# 05_COTS_Avionics.net
KiCad netlist of a schematic drawn in Altium Designer
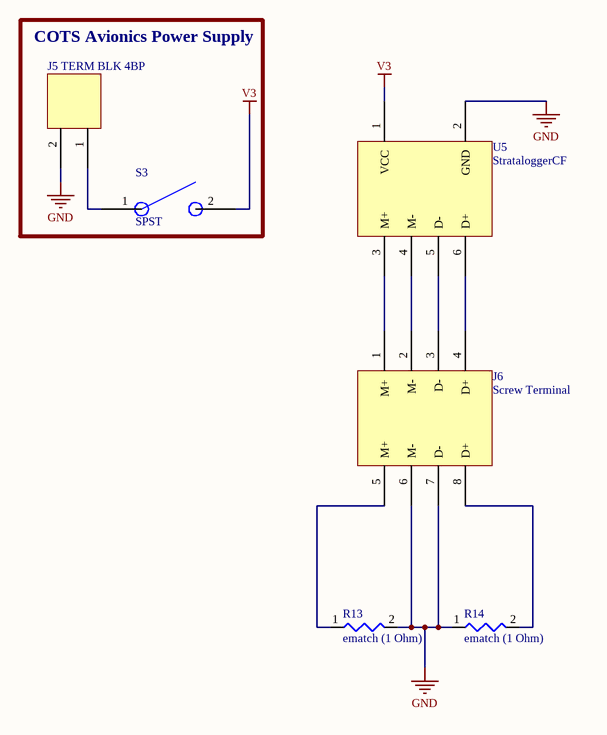
[diagram p0: 05_COTS_Avionics.SchDoc]

(export (version "E")
  (design (tool "Eeschema 10.0.6"))
  (components
    (comp (ref "J5")
      (value "TERM BLK 4BP")
      (footprint "PCB TERM BLK 2P 2.54MM")
      (fields
        (field (name "MANUFACTURER") "TE Connectivity")
        (field (name "MANUFACTURER PART NUMBER") "282834-2")
        (field (name "VOLTAGE") "150V")
      )
      (libsource (lib "SRAD_SAC_Schlib") (part "PCB TERM BLK 2P 2.54MM"))
    )
    (comp (ref "J6")
      (value "Screw Terminal")
      (footprint "Barrier Screw Terminal")
      (libsource (lib "SRAD_SAC_Schlib") (part "Barrier Screw Terminal"))
    )
    (comp (ref "R13")
      (value "ematch (1 Ohm)")
      (footprint "ematch")
      (description "ematch of 1.0-1.5 Ohms of resistance that lights black powder ejection charges.")
      (libsource (lib "SRAD_SAC_Schlib") (part "ematch"))
    )
    (comp (ref "R14")
      (value "ematch (1 Ohm)")
      (footprint "ematch")
      (description "ematch of 1.0-1.5 Ohms of resistance that lights black powder ejection charges.")
      (libsource (lib "SRAD_SAC_Schlib") (part "ematch"))
    )
    (comp (ref "S3")
      (value "SPST")
      (footprint "SPST Switch")
      (description "SPST Switch")
      (libsource (lib "SRAD_SAC_Schlib") (part "SPST Switch"))
    )
    (comp (ref "U5")
      (value "StrataloggerCF")
      (footprint "StrataloggerCF")
      (description "PerfectFlite StrataloggerCF COTS altimeter.")
      (libsource (lib "SRAD_SAC_Schlib") (part "StrataloggerCF"))
    )
  )
  (nets
    (net (code "1") (name "GND") (class "Default")
      (node (ref "J5") (pin "2") (pinfunction "-_2") (pintype "passive"))
      (node (ref "J6") (pin "6") (pinfunction "M-_6") (pintype "passive"))
      (node (ref "J6") (pin "7") (pinfunction "D-_7") (pintype "passive"))
      (node (ref "R13") (pin "2") (pinfunction "-_2") (pintype "passive"))
      (node (ref "R14") (pin "1") (pinfunction "+_1") (pintype "passive"))
      (node (ref "U5") (pin "2") (pinfunction "GND_2") (pintype "passive"))
    )
    (net (code "2") (name "Net-(J5-+)") (class "Default")
      (node (ref "J5") (pin "1") (pinfunction "+_1") (pintype "passive"))
      (node (ref "S3") (pin "1") (pinfunction "+_1") (pintype "passive"))
    )
    (net (code "3") (name "Net-(R13-+)") (class "Default")
      (node (ref "J6") (pin "5") (pinfunction "M+_5") (pintype "passive"))
      (node (ref "R13") (pin "1") (pinfunction "+_1") (pintype "passive"))
    )
    (net (code "4") (name "Net-(R14--)") (class "Default")
      (node (ref "J6") (pin "8") (pinfunction "D+_8") (pintype "passive"))
      (node (ref "R14") (pin "2") (pinfunction "-_2") (pintype "passive"))
    )
    (net (code "5") (name "Net-(U5-D+)") (class "Default")
      (node (ref "J6") (pin "4") (pinfunction "D+_4") (pintype "passive"))
      (node (ref "U5") (pin "6") (pinfunction "D+_6") (pintype "passive"))
    )
    (net (code "6") (name "Net-(U5-D-)") (class "Default")
      (node (ref "J6") (pin "3") (pinfunction "D-_3") (pintype "passive"))
      (node (ref "U5") (pin "5") (pinfunction "D-_5") (pintype "passive"))
    )
    (net (code "7") (name "Net-(U5-M+)") (class "Default")
      (node (ref "J6") (pin "1") (pinfunction "M+_1") (pintype "passive"))
      (node (ref "U5") (pin "3") (pinfunction "M+_3") (pintype "passive"))
    )
    (net (code "8") (name "Net-(U5-M-)") (class "Default")
      (node (ref "J6") (pin "2") (pinfunction "M-_2") (pintype "passive"))
      (node (ref "U5") (pin "4") (pinfunction "M-_4") (pintype "passive"))
    )
    (net (code "9") (name "V3") (class "Default")
      (node (ref "S3") (pin "2") (pinfunction "-_2") (pintype "passive"))
      (node (ref "U5") (pin "1") (pinfunction "VCC_1") (pintype "passive"))
    )
  )
)
